# design.net
KiCad netlist of a schematic drawn in Altium Designer
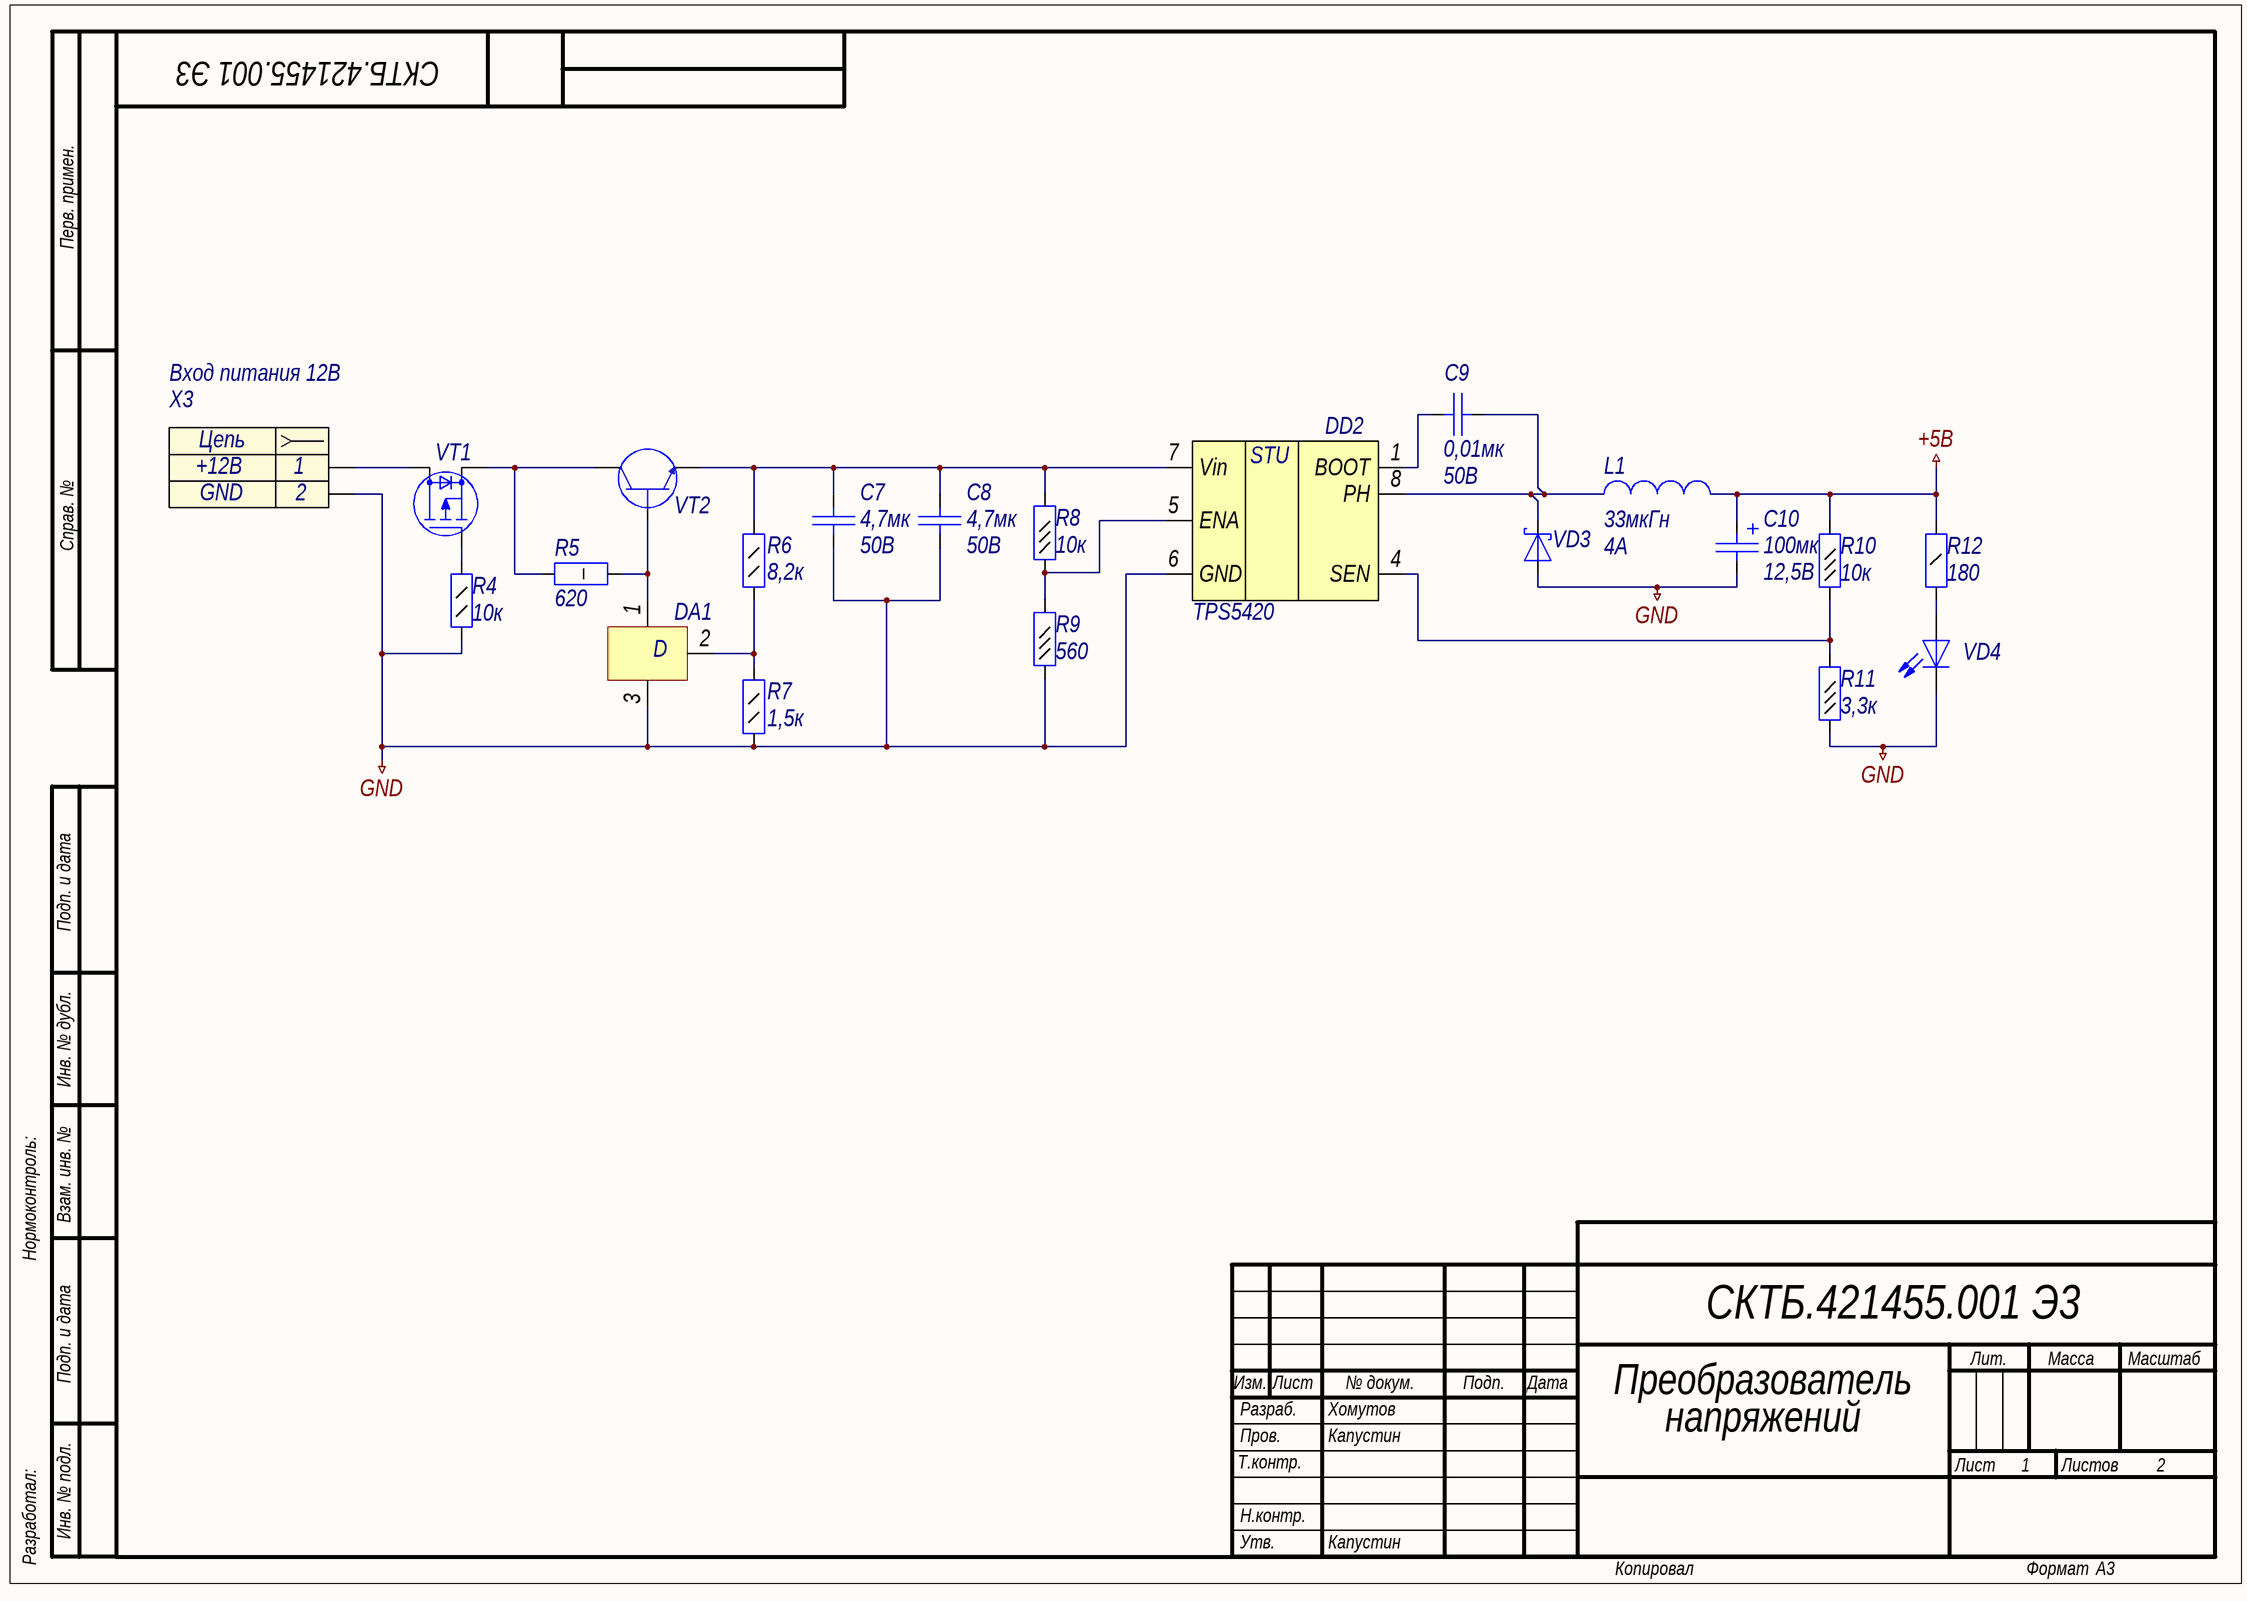
[diagram p0: Преобразователь напряжения.SchDoc]

(export (version "E")
  (design (tool "Eeschema 10.0.6"))
  (components
    (comp (ref "C7")
      (value "4,7мк")
      (footprint "C1206")
      (description "Конденсатор")
      (fields
        (field (name "VOLTAGE") "50В")
        (field (name "PART NUMBER") "GRM31CR71H475KA12L")
        (field (name "Comment") "Capacitor")
      )
      (libsource (lib "MOP44") (part "Capacitor"))
    )
    (comp (ref "C8")
      (value "4,7мк")
      (footprint "C1206")
      (description "Конденсатор")
      (fields
        (field (name "VOLTAGE") "50В")
        (field (name "PART NUMBER") "GRM31CR71H475KA12L")
        (field (name "Comment") "Capacitor")
      )
      (libsource (lib "MOP44") (part "Capacitor"))
    )
    (comp (ref "C9")
      (value "0,01мк")
      (footprint "C0402")
      (description "Конденсатор")
      (fields
        (field (name "VOLTAGE") "50B")
        (field (name "PART NUMBER") "GRM155R71H103K")
        (field (name "Comment") "Capacitor")
      )
      (libsource (lib "MOP44") (part "Capacitor"))
    )
    (comp (ref "C10")
      (value "100мк")
      (footprint "TANTAL CASE E")
      (description "Конденсатор полярный")
      (fields
        (field (name "VOLTAGE") "12,5В")
        (field (name "PART NUMBER") "ECASD91B107M012K00")
        (field (name "Comment") "Capacitor_pol")
      )
      (libsource (lib "MOP44") (part "Capacitor_pol"))
    )
    (comp (ref "DA1")
      (value "TL431")
      (footprint "SOT23-3")
      (description "Программируемый стабилитрон")
      (fields (field (name "PART NUMBER") "TL431ACDBZR"))
      (libsource (lib "MOP44") (part "TL431"))
    )
    (comp (ref "DD2")
      (value "TPS5420")
      (footprint "SO8")
      (description "2-A, WIDE INPUT RANGE, STEP-DOWN CONVERTER")
      (fields (field (name "MANUFACTURER") "Texas Instruments"))
      (libsource (lib "MOP44") (part "TPS5420"))
    )
    (comp (ref "L1")
      (value "33мкГн")
      (footprint "L4040")
      (description "EMI Suppression Filter")
      (fields
        (field (name "RATED CURRENT") "4A")
        (field (name "PART NUMBER") "IHLP4040DZER330M11")
        (field (name "Comment") "Inductor")
      )
      (libsource (lib "MOP44") (part "Inductor"))
    )
    (comp (ref "R4")
      (value "10к")
      (footprint "R0805")
      (description "Резистор")
      (fields (field (name "PART NUMBER") "RC0805FR-07100KL") (field (name "POWER") "0,125Вт"))
      (libsource (lib "MOP44") (part "Resistor_0,125Вт"))
    )
    (comp (ref "R5")
      (value "620")
      (footprint "R2512")
      (description "Резистор")
      (fields (field (name "PART NUMBER") "RC2512FR-07620RL") (field (name "POWER") "1Вт"))
      (libsource (lib "MOP44") (part "Resistor_1Вт"))
    )
    (comp (ref "R6")
      (value "8,2к")
      (footprint "R0805")
      (description "Резистор")
      (fields (field (name "PART NUMBER") "RC0805FR-078K2") (field (name "POWER") "0,125Вт"))
      (libsource (lib "MOP44") (part "Resistor_0,125Вт"))
    )
    (comp (ref "R7")
      (value "1,5к")
      (footprint "R0805")
      (description "Резистор")
      (fields (field (name "PART NUMBER") "RC0805FR-071K5") (field (name "POWER") "0,125Вт"))
      (libsource (lib "MOP44") (part "Resistor_0,125Вт"))
    )
    (comp (ref "R8")
      (value "10к")
      (footprint "R0402")
      (description "Резистор")
      (fields (field (name "PART NUMBER") "RC0402FR-0710KL") (field (name "POWER") "0,062Вт"))
      (libsource (lib "MOP44") (part "Resistor_0,062Вт"))
    )
    (comp (ref "R9")
      (value "560")
      (footprint "R0402")
      (description "Резистор")
      (fields (field (name "PART NUMBER") "RC0402FR-07560RL") (field (name "POWER") "0,062Вт"))
      (libsource (lib "MOP44") (part "Resistor_0,062Вт"))
    )
    (comp (ref "R10")
      (value "10к")
      (footprint "R0402")
      (description "Резистор")
      (fields (field (name "PART NUMBER") "RC0402FR-0710KL") (field (name "POWER") "0,062Вт"))
      (libsource (lib "MOP44") (part "Resistor_0,062Вт"))
    )
    (comp (ref "R11")
      (value "3,3к")
      (footprint "R0402")
      (description "Резистор")
      (fields (field (name "PART NUMBER") "RC0402FR-072K3") (field (name "POWER") "0,062Вт"))
      (libsource (lib "MOP44") (part "Resistor_0,062Вт"))
    )
    (comp (ref "R12")
      (value "180")
      (footprint "R1206")
      (description "Резистор")
      (fields (field (name "PART NUMBER") "RC1206FR-07180RL") (field (name "POWER") "0,25Вт"))
      (libsource (lib "MOP44") (part "Resistor_0,25Вт"))
    )
    (comp (ref "VD3")
      (value "DiodeSchottky")
      (footprint "SMA")
      (description "Диод Шоттки")
      (fields (field (name "PART NUMBER") "SK34A"))
      (libsource (lib "MOP44") (part "DiodeSchottky"))
    )
    (comp (ref "VD4")
      (value "LED")
      (footprint "L_0805")
      (description "Светодиод")
      (fields (field (name "PART NUMBER") "KP-2012EC"))
      (libsource (lib "MOP44") (part "LED"))
    )
    (comp (ref "VT1")
      (value "P-MOSFET")
      (footprint "HD-1")
      (description "N-MOSFET")
      (fields (field (name "PART NUMBER") "IRFD9024PBF") (field (name "MANUFACTURER") "Vishay"))
      (libsource (lib "MOP44") (part "P-MOSFET"))
    )
    (comp (ref "VT2")
      (value "BJT NPN")
      (footprint "SOT-223")
      (fields (field (name "POWER") "2Вт") (field (name "PART NUMBER") "PBSS4540Z.115"))
      (libsource (lib "MOP44") (part "BJT NPN"))
    )
    (comp (ref "X3")
      (value "Вход питания 12В")
      (footprint "DS-210")
      (description "Разъем - 2 конт. розетка")
      (fields (field (name "PART NUMBER") "DS-210B(PBT)(NB)"))
      (libsource (lib "MOP44") (part "Header_2_sct"))
    )
  )
  (nets
    (net (code "1") (name "+5В") (class "Default")
      (node (ref "C10") (pin "1") (pinfunction "1_1") (pintype "passive"))
      (node (ref "L1") (pin "2") (pinfunction "2_2") (pintype "passive"))
      (node (ref "R10") (pin "2") (pinfunction "2_2") (pintype "passive"))
      (node (ref "R12") (pin "2") (pinfunction "2_2") (pintype "passive"))
    )
    (net (code "2") (name "GND") (class "Default")
      (node (ref "C10") (pin "2") (pinfunction "2_2") (pintype "passive"))
      (node (ref "C7") (pin "1") (pinfunction "1_1") (pintype "passive"))
      (node (ref "C8") (pin "1") (pinfunction "1_1") (pintype "passive"))
      (node (ref "DA1") (pin "3") (pinfunction "3_3") (pintype "passive"))
      (node (ref "DD2") (pin "6") (pinfunction "GND_6") (pintype "passive"))
      (node (ref "R11") (pin "1") (pinfunction "1_1") (pintype "passive"))
      (node (ref "R4") (pin "1") (pinfunction "1_1") (pintype "passive"))
      (node (ref "R7") (pin "1") (pinfunction "1_1") (pintype "passive"))
      (node (ref "R9") (pin "1") (pinfunction "1_1") (pintype "passive"))
      (node (ref "VD3") (pin "2") (pinfunction "A_2") (pintype "passive"))
      (node (ref "VD4") (pin "1") (pinfunction "K_1") (pintype "passive"))
      (node (ref "X3") (pin "2") (pinfunction "2_2") (pintype "passive"))
    )
    (net (code "3") (name "Net-(DA1-Pad2)") (class "Default")
      (node (ref "DA1") (pin "2") (pinfunction "2_2") (pintype "passive"))
      (node (ref "R6") (pin "1") (pinfunction "1_1") (pintype "passive"))
      (node (ref "R7") (pin "2") (pinfunction "2_2") (pintype "passive"))
    )
    (net (code "4") (name "Net-(DD2-BOOT)") (class "Default")
      (node (ref "C9") (pin "2") (pinfunction "2_2") (pintype "passive"))
      (node (ref "DD2") (pin "1") (pinfunction "BOOT_1") (pintype "passive"))
    )
    (net (code "5") (name "Net-(DD2-ENA)") (class "Default")
      (node (ref "DD2") (pin "5") (pinfunction "ENA_5") (pintype "passive"))
      (node (ref "R8") (pin "1") (pinfunction "1_1") (pintype "passive"))
      (node (ref "R9") (pin "2") (pinfunction "2_2") (pintype "passive"))
    )
    (net (code "6") (name "Net-(DD2-PH)") (class "Default")
      (node (ref "C9") (pin "1") (pinfunction "1_1") (pintype "passive"))
      (node (ref "DD2") (pin "8") (pinfunction "PH_8") (pintype "passive"))
      (node (ref "L1") (pin "1") (pinfunction "1_1") (pintype "passive"))
      (node (ref "VD3") (pin "1") (pinfunction "K_1") (pintype "passive"))
    )
    (net (code "7") (name "Net-(DD2-SEN)") (class "Default")
      (node (ref "DD2") (pin "4") (pinfunction "SEN_4") (pintype "passive"))
      (node (ref "R10") (pin "1") (pinfunction "1_1") (pintype "passive"))
      (node (ref "R11") (pin "2") (pinfunction "2_2") (pintype "passive"))
    )
    (net (code "8") (name "Net-(DD2-Vin)") (class "Default")
      (node (ref "C7") (pin "2") (pinfunction "2_2") (pintype "passive"))
      (node (ref "C8") (pin "2") (pinfunction "2_2") (pintype "passive"))
      (node (ref "DD2") (pin "7") (pinfunction "Vin_7") (pintype "passive"))
      (node (ref "R6") (pin "2") (pinfunction "2_2") (pintype "passive"))
      (node (ref "R8") (pin "2") (pinfunction "2_2") (pintype "passive"))
      (node (ref "VT2") (pin "2") (pinfunction "2_2") (pintype "passive"))
    )
    (net (code "9") (name "Net-(R5-5)") (class "Default")
      (node (ref "DA1") (pin "1") (pinfunction "1_1") (pintype "passive"))
      (node (ref "R5") (pin "2") (pinfunction "5_2") (pintype "passive"))
      (node (ref "VT2") (pin "1") (pinfunction "1_1") (pintype "passive"))
    )
    (net (code "10") (name "Net-(VD4-A)") (class "Default")
      (node (ref "R12") (pin "1") (pinfunction "1_1") (pintype "passive"))
      (node (ref "VD4") (pin "2") (pinfunction "A_2") (pintype "passive"))
    )
    (net (code "11") (name "Net-(VT1-D)") (class "Default")
      (node (ref "VT1") (pin "3") (pinfunction "D_3") (pintype "passive"))
      (node (ref "X3") (pin "1") (pinfunction "1_1") (pintype "passive"))
    )
    (net (code "12") (name "Net-(VT1-G)") (class "Default")
      (node (ref "R4") (pin "2") (pinfunction "2_2") (pintype "passive"))
      (node (ref "VT1") (pin "1") (pinfunction "G_1") (pintype "passive"))
    )
    (net (code "13") (name "Net-(VT1-S)") (class "Default")
      (node (ref "R5") (pin "1") (pinfunction "1_1") (pintype "passive"))
      (node (ref "VT1") (pin "2") (pinfunction "S_2") (pintype "passive"))
      (node (ref "VT2") (pin "3") (pinfunction "3_3") (pintype "passive"))
    )
  )
)
